# untitled.net
KiCad netlist of a schematic drawn in EAGLE
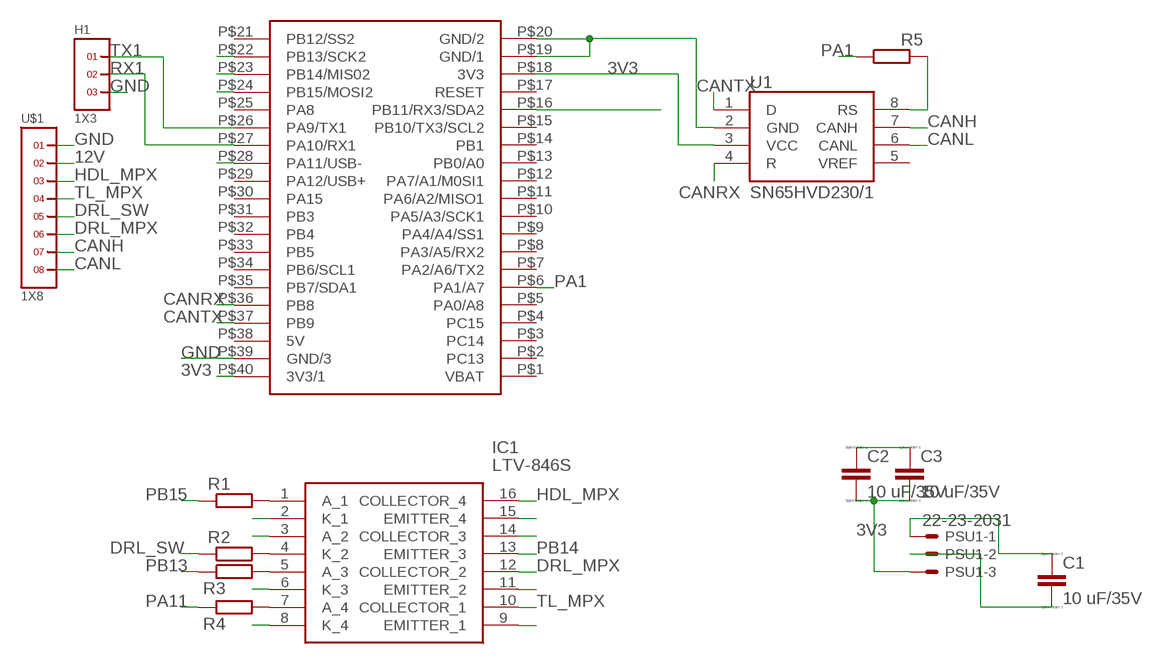
[diagram p0: schematic, sheet 1]

(export (version "E")
  (design (tool "Eeschema 10.0.6"))
  (components
    (comp (ref "C1")
      (value "10 uF/35V")
      (footprint "eagle-import:C1206")
      (libsource (lib "eagle-import") (part "CC1206"))
    )
    (comp (ref "C2")
      (value "10 uF/35V")
      (footprint "eagle-import:C1206")
      (libsource (lib "eagle-import") (part "CC1206"))
    )
    (comp (ref "C3")
      (value "10 uF/35V")
      (footprint "eagle-import:C1206")
      (libsource (lib "eagle-import") (part "CC1206"))
    )
    (comp (ref "H1")
      (value "1X3")
      (footprint "eagle-import:1X3")
      (libsource (lib "eagle-import") (part "1X3"))
    )
    (comp (ref "IC1")
      (value "LTV-846S")
      (footprint "eagle-import:SOP254P1016X460-16N")
      (fields (field (name "MOUSER_PART_NUMBER") "859-LTV-846S") (field (name "RS_PART_NUMBER") "1689678"))
      (libsource (lib "eagle-import") (part "LTV-846S"))
    )
    (comp (ref "PSU1")
      (value "22-23-2031")
      (footprint "eagle-import:22-23-2031")
      (fields (field (name "MF") "MOLEX"))
      (libsource (lib "eagle-import") (part "22-23-2031"))
    )
    (comp (ref "R1")
      (value "47 ohm")
      (footprint "eagle-import:R1206")
      (libsource (lib "eagle-import") (part "R-EU_R1206"))
    )
    (comp (ref "R2")
      (value "1k ohm")
      (footprint "eagle-import:R1206")
      (libsource (lib "eagle-import") (part "R-EU_R1206"))
    )
    (comp (ref "R3")
      (value "47 ohm")
      (footprint "eagle-import:R1206")
      (libsource (lib "eagle-import") (part "R-EU_R1206"))
    )
    (comp (ref "R4")
      (value "47 ohm")
      (footprint "eagle-import:R1206")
      (libsource (lib "eagle-import") (part "R-EU_R1206"))
    )
    (comp (ref "R5")
      (value "47k ohm")
      (footprint "eagle-import:R1206")
      (libsource (lib "eagle-import") (part "R-EU_R1206"))
    )
    (comp (ref "STM32")
      (value "BLUEPILL")
      (footprint "eagle-import:40-DIP-BLUE-PIL")
      (libsource (lib "eagle-import") (part "BLUEPILL"))
    )
    (comp (ref "U$1")
      (value "1X8")
      (footprint "eagle-import:1X8")
      (libsource (lib "eagle-import") (part "1X8"))
    )
    (comp (ref "U1")
      (value "SN65HVD230/1")
      (footprint "eagle-import:SO8")
      (libsource (lib "eagle-import") (part "SN65HVD230/1"))
    )
  )
  (nets
    (net (code "1") (name "/3V3") (class "Default")
      (node (ref "C2") (pin "2") (pinfunction "2_2") (pintype "passive"))
      (node (ref "C3") (pin "2") (pinfunction "2_2") (pintype "passive"))
      (node (ref "IC1") (pin "14") (pinfunction "COLLECTOR_3_14") (pintype "bidirectional"))
      (node (ref "IC1") (pin "3") (pinfunction "A_2_3") (pintype "bidirectional"))
      (node (ref "PSU1") (pin "3") (pinfunction "S_3") (pintype "passive"))
      (node (ref "STM32") (pin "P$18") (pinfunction "3V3_P$18") (pintype "bidirectional"))
      (node (ref "STM32") (pin "P$40") (pinfunction "3V3/1_P$40") (pintype "bidirectional"))
      (node (ref "U1") (pin "3") (pinfunction "VCC_3") (pintype "power_in"))
    )
    (net (code "2") (name "/12V") (class "Default")
      (node (ref "C1") (pin "1") (pinfunction "1_1") (pintype "passive"))
      (node (ref "PSU1") (pin "1") (pinfunction "S_1") (pintype "passive"))
      (node (ref "U$1") (pin "2") (pinfunction "2_2") (pintype "bidirectional"))
    )
    (net (code "3") (name "/CANH") (class "Default")
      (node (ref "U$1") (pin "7") (pinfunction "7_7") (pintype "bidirectional"))
      (node (ref "U1") (pin "7") (pinfunction "CANH_7") (pintype "bidirectional"))
    )
    (net (code "4") (name "/CANL") (class "Default")
      (node (ref "U$1") (pin "8") (pinfunction "8_8") (pintype "bidirectional"))
      (node (ref "U1") (pin "6") (pinfunction "CANL_6") (pintype "bidirectional"))
    )
    (net (code "5") (name "/CANRX") (class "Default")
      (node (ref "STM32") (pin "P$36") (pinfunction "PB8_P$36") (pintype "bidirectional"))
      (node (ref "U1") (pin "4") (pinfunction "R_4") (pintype "bidirectional"))
    )
    (net (code "6") (name "/CANTX") (class "Default")
      (node (ref "STM32") (pin "P$37") (pinfunction "PB9_P$37") (pintype "bidirectional"))
      (node (ref "U1") (pin "1") (pinfunction "D_1") (pintype "bidirectional"))
    )
    (net (code "7") (name "/DRL_MPX") (class "Default")
      (node (ref "IC1") (pin "12") (pinfunction "COLLECTOR_2_12") (pintype "bidirectional"))
      (node (ref "U$1") (pin "6") (pinfunction "6_6") (pintype "bidirectional"))
    )
    (net (code "8") (name "/DRL_SW") (class "Default")
      (node (ref "R2") (pin "1") (pinfunction "1_1") (pintype "passive"))
      (node (ref "U$1") (pin "5") (pinfunction "5_5") (pintype "bidirectional"))
    )
    (net (code "9") (name "/GND") (class "Default")
      (node (ref "C1") (pin "2") (pinfunction "2_2") (pintype "passive"))
      (node (ref "C2") (pin "1") (pinfunction "1_1") (pintype "passive"))
      (node (ref "C3") (pin "1") (pinfunction "1_1") (pintype "passive"))
      (node (ref "H1") (pin "3") (pinfunction "3_3") (pintype "bidirectional"))
      (node (ref "IC1") (pin "11") (pinfunction "EMITTER_2_11") (pintype "bidirectional"))
      (node (ref "IC1") (pin "15") (pinfunction "EMITTER_4_15") (pintype "bidirectional"))
      (node (ref "IC1") (pin "2") (pinfunction "K_1_2") (pintype "bidirectional"))
      (node (ref "IC1") (pin "6") (pinfunction "K_3_6") (pintype "bidirectional"))
      (node (ref "IC1") (pin "8") (pinfunction "K_4_8") (pintype "bidirectional"))
      (node (ref "IC1") (pin "9") (pinfunction "EMITTER_1_9") (pintype "bidirectional"))
      (node (ref "PSU1") (pin "2") (pinfunction "S_2") (pintype "passive"))
      (node (ref "STM32") (pin "P$19") (pinfunction "GND/1_P$19") (pintype "bidirectional"))
      (node (ref "STM32") (pin "P$20") (pinfunction "GND/2_P$20") (pintype "bidirectional"))
      (node (ref "STM32") (pin "P$39") (pinfunction "GND/3_P$39") (pintype "bidirectional"))
      (node (ref "U$1") (pin "1") (pinfunction "1_1") (pintype "bidirectional"))
      (node (ref "U1") (pin "2") (pinfunction "GND_2") (pintype "power_in"))
    )
    (net (code "10") (name "/HDL_MPX") (class "Default")
      (node (ref "IC1") (pin "16") (pinfunction "COLLECTOR_4_16") (pintype "bidirectional"))
      (node (ref "U$1") (pin "3") (pinfunction "3_3") (pintype "bidirectional"))
    )
    (net (code "11") (name "/PA1") (class "Default")
      (node (ref "R5") (pin "1") (pinfunction "1_1") (pintype "passive"))
      (node (ref "STM32") (pin "P$6") (pinfunction "PA1/A7_P$6") (pintype "bidirectional"))
    )
    (net (code "12") (name "/PA11") (class "Default")
      (node (ref "R4") (pin "1") (pinfunction "1_1") (pintype "passive"))
      (node (ref "STM32") (pin "P$28") (pinfunction "PA11/USB-_P$28") (pintype "bidirectional"))
    )
    (net (code "13") (name "/PB13") (class "Default")
      (node (ref "R3") (pin "1") (pinfunction "1_1") (pintype "passive"))
      (node (ref "STM32") (pin "P$22") (pinfunction "PB13/SCK2_P$22") (pintype "bidirectional"))
    )
    (net (code "14") (name "/PB14") (class "Default")
      (node (ref "IC1") (pin "13") (pinfunction "EMITTER_3_13") (pintype "bidirectional"))
      (node (ref "STM32") (pin "P$23") (pinfunction "PB14/MIS02_P$23") (pintype "bidirectional"))
    )
    (net (code "15") (name "/PB15") (class "Default")
      (node (ref "R1") (pin "1") (pinfunction "1_1") (pintype "passive"))
      (node (ref "STM32") (pin "P$24") (pinfunction "PB15/MOSI2_P$24") (pintype "bidirectional"))
    )
    (net (code "16") (name "/RX1") (class "Default")
      (node (ref "H1") (pin "2") (pinfunction "2_2") (pintype "bidirectional"))
      (node (ref "STM32") (pin "P$27") (pinfunction "PA10/RX1_P$27") (pintype "bidirectional"))
    )
    (net (code "17") (name "/TL_MPX") (class "Default")
      (node (ref "IC1") (pin "10") (pinfunction "COLLECTOR_1_10") (pintype "bidirectional"))
      (node (ref "U$1") (pin "4") (pinfunction "4_4") (pintype "bidirectional"))
    )
    (net (code "18") (name "/TX1") (class "Default")
      (node (ref "H1") (pin "1") (pinfunction "1_1") (pintype "bidirectional"))
      (node (ref "STM32") (pin "P$26") (pinfunction "PA9/TX1_P$26") (pintype "bidirectional"))
    )
    (net (code "19") (name "Net-(IC1-A_1)") (class "Default")
      (node (ref "IC1") (pin "1") (pinfunction "A_1_1") (pintype "bidirectional"))
      (node (ref "R1") (pin "2") (pinfunction "2_2") (pintype "passive"))
    )
    (net (code "20") (name "Net-(IC1-A_3)") (class "Default")
      (node (ref "IC1") (pin "5") (pinfunction "A_3_5") (pintype "bidirectional"))
      (node (ref "R3") (pin "2") (pinfunction "2_2") (pintype "passive"))
    )
    (net (code "21") (name "Net-(IC1-A_4)") (class "Default")
      (node (ref "IC1") (pin "7") (pinfunction "A_4_7") (pintype "bidirectional"))
      (node (ref "R4") (pin "2") (pinfunction "2_2") (pintype "passive"))
    )
    (net (code "22") (name "Net-(IC1-K_2)") (class "Default")
      (node (ref "IC1") (pin "4") (pinfunction "K_2_4") (pintype "bidirectional"))
      (node (ref "R2") (pin "2") (pinfunction "2_2") (pintype "passive"))
    )
    (net (code "23") (name "Net-(U1-RS)") (class "Default")
      (node (ref "R5") (pin "2") (pinfunction "2_2") (pintype "passive"))
      (node (ref "U1") (pin "8") (pinfunction "RS_8") (pintype "bidirectional"))
    )
    (net (code "24") (name "unconnected-(STM32-5V-PadP$38)") (class "Default")
      (node (ref "STM32") (pin "P$38") (pinfunction "5V_P$38") (pintype "bidirectional"))
    )
    (net (code "25") (name "unconnected-(STM32-PA0{slash}A8-PadP$5)") (class "Default")
      (node (ref "STM32") (pin "P$5") (pinfunction "PA0/A8_P$5") (pintype "bidirectional"))
    )
    (net (code "26") (name "unconnected-(STM32-PA2{slash}A6{slash}TX2-PadP$7)") (class "Default")
      (node (ref "STM32") (pin "P$7") (pinfunction "PA2/A6/TX2_P$7") (pintype "bidirectional"))
    )
    (net (code "27") (name "unconnected-(STM32-PA3{slash}A5{slash}RX2-PadP$8)") (class "Default")
      (node (ref "STM32") (pin "P$8") (pinfunction "PA3/A5/RX2_P$8") (pintype "bidirectional"))
    )
    (net (code "28") (name "unconnected-(STM32-PA4{slash}A4{slash}SS1-PadP$9)") (class "Default")
      (node (ref "STM32") (pin "P$9") (pinfunction "PA4/A4/SS1_P$9") (pintype "bidirectional"))
    )
    (net (code "29") (name "unconnected-(STM32-PA5{slash}A3{slash}SCK1-PadP$10)") (class "Default")
      (node (ref "STM32") (pin "P$10") (pinfunction "PA5/A3/SCK1_P$10") (pintype "bidirectional"))
    )
    (net (code "30") (name "unconnected-(STM32-PA6{slash}A2{slash}MISO1-PadP$11)") (class "Default")
      (node (ref "STM32") (pin "P$11") (pinfunction "PA6/A2/MISO1_P$11") (pintype "bidirectional"))
    )
    (net (code "31") (name "unconnected-(STM32-PA7{slash}A1{slash}M0SI1-PadP$12)") (class "Default")
      (node (ref "STM32") (pin "P$12") (pinfunction "PA7/A1/M0SI1_P$12") (pintype "bidirectional"))
    )
    (net (code "32") (name "unconnected-(STM32-PA8-PadP$25)") (class "Default")
      (node (ref "STM32") (pin "P$25") (pinfunction "PA8_P$25") (pintype "bidirectional"))
    )
    (net (code "33") (name "unconnected-(STM32-PA12{slash}USB+-PadP$29)") (class "Default")
      (node (ref "STM32") (pin "P$29") (pinfunction "PA12/USB+_P$29") (pintype "bidirectional"))
    )
    (net (code "34") (name "unconnected-(STM32-PA15-PadP$30)") (class "Default")
      (node (ref "STM32") (pin "P$30") (pinfunction "PA15_P$30") (pintype "bidirectional"))
    )
    (net (code "35") (name "unconnected-(STM32-PB0{slash}A0-PadP$13)") (class "Default")
      (node (ref "STM32") (pin "P$13") (pinfunction "PB0/A0_P$13") (pintype "bidirectional"))
    )
    (net (code "36") (name "unconnected-(STM32-PB1-PadP$14)") (class "Default")
      (node (ref "STM32") (pin "P$14") (pinfunction "PB1_P$14") (pintype "bidirectional"))
    )
    (net (code "37") (name "unconnected-(STM32-PB3-PadP$31)") (class "Default")
      (node (ref "STM32") (pin "P$31") (pinfunction "PB3_P$31") (pintype "bidirectional"))
    )
    (net (code "38") (name "unconnected-(STM32-PB4-PadP$32)") (class "Default")
      (node (ref "STM32") (pin "P$32") (pinfunction "PB4_P$32") (pintype "bidirectional"))
    )
    (net (code "39") (name "unconnected-(STM32-PB5-PadP$33)") (class "Default")
      (node (ref "STM32") (pin "P$33") (pinfunction "PB5_P$33") (pintype "bidirectional"))
    )
    (net (code "40") (name "unconnected-(STM32-PB6{slash}SCL1-PadP$34)") (class "Default")
      (node (ref "STM32") (pin "P$34") (pinfunction "PB6/SCL1_P$34") (pintype "bidirectional"))
    )
    (net (code "41") (name "unconnected-(STM32-PB7{slash}SDA1-PadP$35)") (class "Default")
      (node (ref "STM32") (pin "P$35") (pinfunction "PB7/SDA1_P$35") (pintype "bidirectional"))
    )
    (net (code "42") (name "unconnected-(STM32-PB10{slash}TX3{slash}SCL2-PadP$15)") (class "Default")
      (node (ref "STM32") (pin "P$15") (pinfunction "PB10/TX3/SCL2_P$15") (pintype "bidirectional"))
    )
    (net (code "43") (name "unconnected-(STM32-PB11{slash}RX3{slash}SDA2-PadP$16)") (class "Default")
      (node (ref "STM32") (pin "P$16") (pinfunction "PB11/RX3/SDA2_P$16") (pintype "bidirectional"))
    )
    (net (code "44") (name "unconnected-(STM32-PB12{slash}SS2-PadP$21)") (class "Default")
      (node (ref "STM32") (pin "P$21") (pinfunction "PB12/SS2_P$21") (pintype "bidirectional"))
    )
    (net (code "45") (name "unconnected-(STM32-PC13-PadP$2)") (class "Default")
      (node (ref "STM32") (pin "P$2") (pinfunction "PC13_P$2") (pintype "bidirectional"))
    )
    (net (code "46") (name "unconnected-(STM32-PC14-PadP$3)") (class "Default")
      (node (ref "STM32") (pin "P$3") (pinfunction "PC14_P$3") (pintype "bidirectional"))
    )
    (net (code "47") (name "unconnected-(STM32-PC15-PadP$4)") (class "Default")
      (node (ref "STM32") (pin "P$4") (pinfunction "PC15_P$4") (pintype "bidirectional"))
    )
    (net (code "48") (name "unconnected-(STM32-RESET-PadP$17)") (class "Default")
      (node (ref "STM32") (pin "P$17") (pinfunction "RESET_P$17") (pintype "bidirectional"))
    )
    (net (code "49") (name "unconnected-(STM32-VBAT-PadP$1)") (class "Default")
      (node (ref "STM32") (pin "P$1") (pinfunction "VBAT_P$1") (pintype "bidirectional"))
    )
    (net (code "50") (name "unconnected-(U1-VREF-Pad5)") (class "Default")
      (node (ref "U1") (pin "5") (pinfunction "VREF_5") (pintype "bidirectional"))
    )
  )
)
